# MIDImike_r4.net
KiCad netlist of a schematic drawn in EAGLE
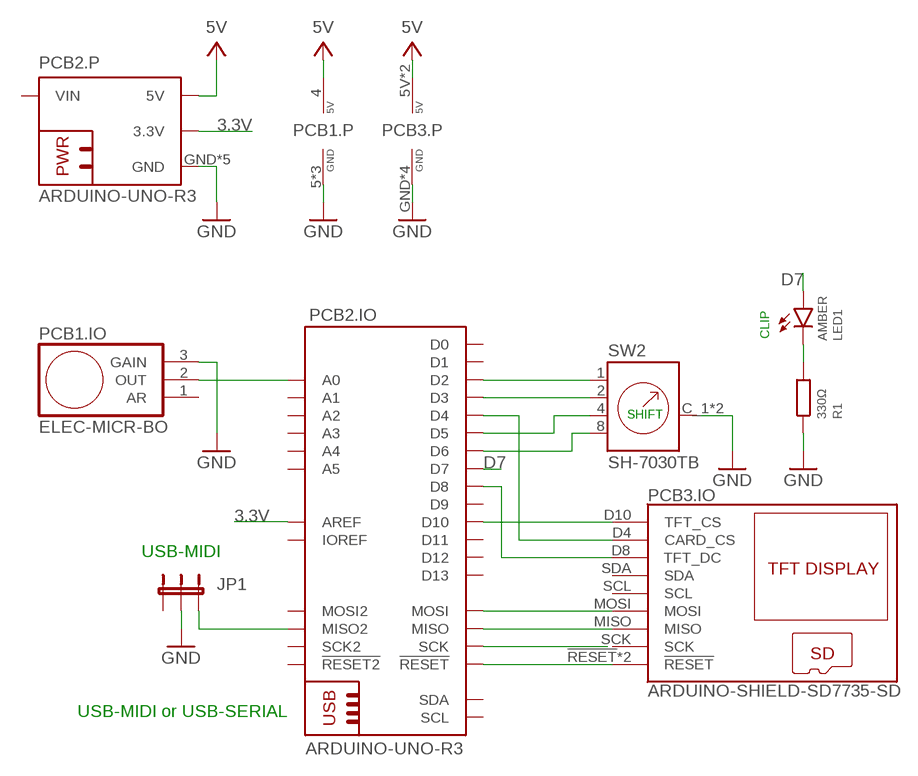
[diagram p0: schematic, sheet 1]

(export (version "E")
  (design (tool "Eeschema 10.0.6"))
  (components
    (comp (ref "JP1")
      (value "JP2E")
      (footprint "eagle-import:JP2")
      (libsource (lib "eagle-import") (part "JP2E"))
    )
    (comp (ref "LED1")
      (value "AMBER")
      (footprint "eagle-import:CHIPLED_0805")
      (libsource (lib "eagle-import") (part "LEDCHIPLED_0805"))
    )
    (comp (ref "PCB1")
      (value "ELEC-MICR-BO")
      (footprint "eagle-import:ELEC_MICR_BREAKOUT")
      (libsource (lib "eagle-import") (part "ELEC-MICR-BO"))
    )
    (comp (ref "PCB2")
      (value "ARDUINO-UNO-R3")
      (footprint "eagle-import:ARDUINO-UNO--R3")
      (libsource (lib "eagle-import") (part "ARDUINO-UNO-R3"))
    )
    (comp (ref "PCB3")
      (value "ARDUINO-SHIELD-SD7735-SD")
      (footprint "eagle-import:ARDIONO-SHIELD")
      (libsource (lib "eagle-import") (part "ARDUINO-SHIELD-SD7735-SD"))
    )
    (comp (ref "R1")
      (value "330Ω")
      (footprint "eagle-import:R0805")
      (fields (field (name "MANF") "Bourns"))
      (libsource (lib "eagle-import") (part "R-EU_R0805"))
    )
    (comp (ref "SW2")
      (value "SH-7030TB")
      (footprint "eagle-import:SW_RDS-16S-1045-SMT-TR")
      (fields (field (name "MF") "CUI Devices") (field (name "MP") "RDS-16S-1045-SMT-TR"))
      (libsource (lib "eagle-import") (part "SH-7030TB"))
    )
  )
  (nets
    (net (code "1") (name "/3.3V") (class "Default")
      (node (ref "PCB2") (pin "3.3V") (pinfunction "3.3V_3.3V") (pintype "power_in"))
      (node (ref "PCB2") (pin "AREF") (pinfunction "AREF_AREF") (pintype "bidirectional"))
    )
    (net (code "2") (name "/D7") (class "Default")
      (node (ref "LED1") (pin "A") (pinfunction "A_A") (pintype "passive"))
      (node (ref "PCB2") (pin "D7") (pinfunction "D7_D7") (pintype "bidirectional"))
    )
    (net (code "3") (name "/VIN") (class "Default")
      (node (ref "PCB2") (pin "VIN") (pinfunction "VIN_VIN") (pintype "power_in"))
    )
    (net (code "4") (name "5V") (class "Default")
      (node (ref "PCB1") (pin "4") (pinfunction "5V_4") (pintype "passive"))
      (node (ref "PCB2") (pin "5V") (pinfunction "5V_5V") (pintype "power_in"))
      (node (ref "PCB2") (pin "5V@1") (pinfunction "5V_5V@1") (pintype "power_in"))
      (node (ref "PCB2") (pin "5V@2") (pinfunction "5V_5V@2") (pintype "power_in"))
      (node (ref "PCB3") (pin "5V") (pinfunction "5V_5V") (pintype "passive"))
      (node (ref "PCB3") (pin "5V@1") (pinfunction "5V_5V@1") (pintype "passive"))
    )
    (net (code "5") (name "GND") (class "Default")
      (node (ref "JP1") (pin "2") (pinfunction "2_2") (pintype "passive"))
      (node (ref "PCB1") (pin "3") (pinfunction "GAIN_3") (pintype "input"))
      (node (ref "PCB1") (pin "5") (pinfunction "GND_5") (pintype "power_in"))
      (node (ref "PCB1") (pin "P$1") (pinfunction "GND_P$1") (pintype "power_in"))
      (node (ref "PCB1") (pin "P$2") (pinfunction "GND_P$2") (pintype "power_in"))
      (node (ref "PCB2") (pin "GND") (pinfunction "GND_GND") (pintype "power_in"))
      (node (ref "PCB2") (pin "GND@1") (pinfunction "GND_GND@1") (pintype "power_in"))
      (node (ref "PCB2") (pin "GND@2") (pinfunction "GND_GND@2") (pintype "power_in"))
      (node (ref "PCB2") (pin "GND@3") (pinfunction "GND_GND@3") (pintype "power_in"))
      (node (ref "PCB2") (pin "GND@4") (pinfunction "GND_GND@4") (pintype "power_in"))
      (node (ref "PCB3") (pin "GND") (pinfunction "GND_GND") (pintype "power_in"))
      (node (ref "PCB3") (pin "GND@1") (pinfunction "GND_GND@1") (pintype "power_in"))
      (node (ref "PCB3") (pin "GND@2") (pinfunction "GND_GND@2") (pintype "power_in"))
      (node (ref "PCB3") (pin "GND@3") (pinfunction "GND_GND@3") (pintype "power_in"))
      (node (ref "R1") (pin "1") (pinfunction "1_1") (pintype "passive"))
      (node (ref "SW2") (pin "C_1") (pinfunction "C_C_1") (pintype "passive"))
      (node (ref "SW2") (pin "C_2") (pinfunction "C_C_2") (pintype "passive"))
    )
    (net (code "6") (name "Net-(JP1-Pad3)") (class "Default")
      (node (ref "JP1") (pin "3") (pinfunction "3_3") (pintype "passive"))
      (node (ref "PCB2") (pin "MISO2") (pinfunction "MISO2_MISO2") (pintype "bidirectional"))
    )
    (net (code "7") (name "Net-(LED1-PadC)") (class "Default")
      (node (ref "LED1") (pin "C") (pinfunction "C_C") (pintype "passive"))
      (node (ref "R1") (pin "2") (pinfunction "2_2") (pintype "passive"))
    )
    (net (code "8") (name "Net-(PCB1A-OUT)") (class "Default")
      (node (ref "PCB1") (pin "2") (pinfunction "OUT_2") (pintype "output"))
      (node (ref "PCB2") (pin "A0") (pinfunction "A0_A0") (pintype "bidirectional"))
    )
    (net (code "9") (name "Net-(PCB2-PadD2)") (class "Default")
      (node (ref "PCB2") (pin "D2") (pinfunction "D2_D2") (pintype "bidirectional"))
      (node (ref "SW2") (pin "1") (pinfunction "1_1") (pintype "passive"))
    )
    (net (code "10") (name "Net-(PCB2-PadD3)") (class "Default")
      (node (ref "PCB2") (pin "D3") (pinfunction "D3_D3") (pintype "bidirectional"))
      (node (ref "SW2") (pin "2") (pinfunction "2_2") (pintype "passive"))
    )
    (net (code "11") (name "Net-(PCB2-PadD5)") (class "Default")
      (node (ref "PCB2") (pin "D5") (pinfunction "D5_D5") (pintype "bidirectional"))
      (node (ref "SW2") (pin "4") (pinfunction "4_4") (pintype "passive"))
    )
    (net (code "12") (name "Net-(PCB2-PadD6)") (class "Default")
      (node (ref "PCB2") (pin "D6") (pinfunction "D6_D6") (pintype "bidirectional"))
      (node (ref "SW2") (pin "8") (pinfunction "8_8") (pintype "passive"))
    )
    (net (code "13") (name "Net-(PCB2-PadMISO)") (class "Default")
      (node (ref "PCB2") (pin "MISO") (pinfunction "MISO_MISO") (pintype "bidirectional"))
      (node (ref "PCB3") (pin "MISO") (pinfunction "MISO_MISO") (pintype "output"))
    )
    (net (code "14") (name "Net-(PCB2-PadMOSI)") (class "Default")
      (node (ref "PCB2") (pin "MOSI") (pinfunction "MOSI_MOSI") (pintype "bidirectional"))
      (node (ref "PCB3") (pin "MOSI") (pinfunction "MOSI_MOSI") (pintype "input"))
    )
    (net (code "15") (name "Net-(PCB2A-~{RESET}-Pad!RESET!)") (class "Default")
      (node (ref "PCB2") (pin "!RESET!") (pinfunction "~{RESET}_!RESET!") (pintype "bidirectional"))
      (node (ref "PCB2") (pin "!RESET!@1") (pinfunction "~{RESET}_!RESET!@1") (pintype "bidirectional"))
      (node (ref "PCB3") (pin "!RESET!") (pinfunction "~{RESET}_!RESET!") (pintype "bidirectional"))
      (node (ref "PCB3") (pin "!RESET!@1") (pinfunction "~{RESET}_!RESET!@1") (pintype "bidirectional"))
    )
    (net (code "16") (name "Net-(PCB3A-CARD_CS)") (class "Default")
      (node (ref "PCB2") (pin "D4") (pinfunction "D4_D4") (pintype "bidirectional"))
      (node (ref "PCB3") (pin "D4") (pinfunction "CARD_CS_D4") (pintype "input"))
    )
    (net (code "17") (name "Net-(PCB3A-TFT_CS)") (class "Default")
      (node (ref "PCB2") (pin "D10") (pinfunction "D10_D10") (pintype "bidirectional"))
      (node (ref "PCB3") (pin "D10") (pinfunction "TFT_CS_D10") (pintype "input"))
    )
    (net (code "18") (name "Net-(PCB3A-TFT_DC)") (class "Default")
      (node (ref "PCB2") (pin "D8") (pinfunction "D8_D8") (pintype "bidirectional"))
      (node (ref "PCB3") (pin "D8") (pinfunction "TFT_DC_D8") (pintype "bidirectional"))
    )
    (net (code "19") (name "unconnected-(JP1-Pad1)") (class "Default")
      (node (ref "JP1") (pin "1") (pinfunction "1_1") (pintype "passive"))
    )
    (net (code "20") (name "unconnected-(PCB1A-AR-Pad1)") (class "Default")
      (node (ref "PCB1") (pin "1") (pinfunction "AR_1") (pintype "input"))
    )
    (net (code "21") (name "unconnected-(PCB2-PadA1)") (class "Default")
      (node (ref "PCB2") (pin "A1") (pinfunction "A1_A1") (pintype "bidirectional"))
    )
    (net (code "22") (name "unconnected-(PCB2-PadA2)") (class "Default")
      (node (ref "PCB2") (pin "A2") (pinfunction "A2_A2") (pintype "bidirectional"))
    )
    (net (code "23") (name "unconnected-(PCB2-PadA3)") (class "Default")
      (node (ref "PCB2") (pin "A3") (pinfunction "A3_A3") (pintype "bidirectional"))
    )
    (net (code "24") (name "unconnected-(PCB2-PadA4)") (class "Default")
      (node (ref "PCB2") (pin "A4") (pinfunction "A4_A4") (pintype "bidirectional"))
    )
    (net (code "25") (name "unconnected-(PCB2-PadA5)") (class "Default")
      (node (ref "PCB2") (pin "A5") (pinfunction "A5_A5") (pintype "bidirectional"))
    )
    (net (code "26") (name "unconnected-(PCB2-PadD0)") (class "Default")
      (node (ref "PCB2") (pin "D0") (pinfunction "D0_D0") (pintype "bidirectional"))
    )
    (net (code "27") (name "unconnected-(PCB2-PadD1)") (class "Default")
      (node (ref "PCB2") (pin "D1") (pinfunction "D1_D1") (pintype "bidirectional"))
    )
    (net (code "28") (name "unconnected-(PCB2-PadD9)") (class "Default")
      (node (ref "PCB2") (pin "D9") (pinfunction "D9_D9") (pintype "bidirectional"))
    )
    (net (code "29") (name "unconnected-(PCB2-PadD11)") (class "Default")
      (node (ref "PCB2") (pin "D11") (pinfunction "D11_D11") (pintype "bidirectional"))
    )
    (net (code "30") (name "unconnected-(PCB2-PadD12)") (class "Default")
      (node (ref "PCB2") (pin "D12") (pinfunction "D12_D12") (pintype "bidirectional"))
    )
    (net (code "31") (name "unconnected-(PCB2-PadD13)") (class "Default")
      (node (ref "PCB2") (pin "D13") (pinfunction "D13_D13") (pintype "bidirectional"))
    )
    (net (code "32") (name "unconnected-(PCB2-PadIOREF)") (class "Default")
      (node (ref "PCB2") (pin "IOREF") (pinfunction "IOREF_IOREF") (pintype "bidirectional"))
    )
    (net (code "33") (name "unconnected-(PCB2-PadMOSI2)") (class "Default")
      (node (ref "PCB2") (pin "MOSI2") (pinfunction "MOSI2_MOSI2") (pintype "bidirectional"))
    )
    (net (code "34") (name "unconnected-(PCB2-PadSCK)") (class "Default")
      (node (ref "PCB2") (pin "SCK") (pinfunction "SCK_SCK") (pintype "bidirectional"))
    )
    (net (code "35") (name "unconnected-(PCB2-PadSCK2)") (class "Default")
      (node (ref "PCB2") (pin "SCK2") (pinfunction "SCK2_SCK2") (pintype "bidirectional"))
    )
    (net (code "36") (name "unconnected-(PCB2-PadSCL)") (class "Default")
      (node (ref "PCB2") (pin "SCL") (pinfunction "SCL_SCL") (pintype "bidirectional"))
    )
    (net (code "37") (name "unconnected-(PCB2-PadSDA)") (class "Default")
      (node (ref "PCB2") (pin "SDA") (pinfunction "SDA_SDA") (pintype "bidirectional"))
    )
    (net (code "38") (name "unconnected-(PCB2A-~{RESET2}-Pad!RESET2!)") (class "Default")
      (node (ref "PCB2") (pin "!RESET2!") (pinfunction "~{RESET2}_!RESET2!") (pintype "bidirectional"))
    )
    (net (code "39") (name "unconnected-(PCB3-PadSCK)") (class "Default")
      (node (ref "PCB3") (pin "SCK") (pinfunction "SCK_SCK") (pintype "input"))
    )
    (net (code "40") (name "unconnected-(PCB3-PadSCL)") (class "Default")
      (node (ref "PCB3") (pin "SCL") (pinfunction "SCL_SCL") (pintype "input"))
    )
    (net (code "41") (name "unconnected-(PCB3-PadSDA)") (class "Default")
      (node (ref "PCB3") (pin "SDA") (pinfunction "SDA_SDA") (pintype "bidirectional"))
    )
  )
)
